# PDB_Schematic_v1_0.net
KiCad netlist of a schematic drawn in Altium Designer
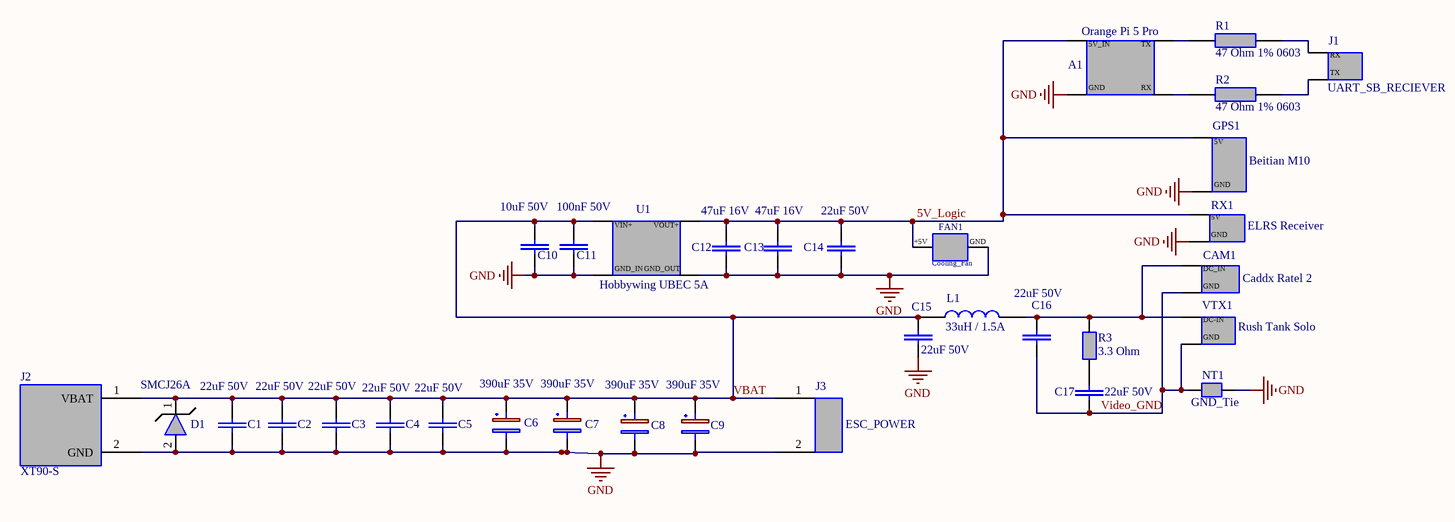
[diagram p0: PDB_Schematic_v1.0.SchDoc]

(export (version "E")
  (design (tool "Eeschema 10.0.6"))
  (components
    (comp (ref "A1")
      (value "Orange Pi 5 Pro")
      (footprint "PDB_Footprints_v1.0:FOOTPRINT_ORANGE_PI")
      (libsource (lib "PDB_Components_v1.0") (part "Orange Pi 5 Pro"))
    )
    (comp (ref "C1")
      (value "22uF 50V")
      (footprint "PDB_Footprints_v1.0:1210")
      (libsource (lib "PDB_Components_v1.0") (part "Cap_MLCC"))
    )
    (comp (ref "C2")
      (value "22uF 50V")
      (footprint "PDB_Footprints_v1.0:1210")
      (libsource (lib "PDB_Components_v1.0") (part "Cap_MLCC"))
    )
    (comp (ref "C3")
      (value "22uF 50V")
      (footprint "PDB_Footprints_v1.0:1210")
      (libsource (lib "PDB_Components_v1.0") (part "Cap_MLCC"))
    )
    (comp (ref "C4")
      (value "22uF 50V")
      (footprint "PDB_Footprints_v1.0:1210")
      (libsource (lib "PDB_Components_v1.0") (part "Cap_Cer_22uF_50V"))
    )
    (comp (ref "C5")
      (value "22uF 50V")
      (footprint "PDB_Footprints_v1.0:1210")
      (libsource (lib "PDB_Components_v1.0") (part "Cap_MLCC"))
    )
    (comp (ref "C6")
      (value "390uF 35V")
      (footprint "PDB_Footprints_v1.0:CAP_ELEC_D10.0_P5.0")
      (description "Low ESR Aluminum Electrolytic Capacitor, Panasonic FR Series, 390uF 35V, Radial, 5mm Lead Pitc")
      (fields (field (name "VOLTAGE") "35V") (field (name "MANUFACTURER") "Panasonic"))
      (libsource (lib "PDB_Components_v1.0") (part "Cap_Low_ESR"))
    )
    (comp (ref "C7")
      (value "390uF 35V")
      (footprint "PDB_Footprints_v1.0:CAP_ELEC_D10.0_P5.0")
      (description "Low ESR Aluminum Electrolytic Capacitor, Panasonic FR Series, 390uF 35V, Radial, 5mm Lead Pitc")
      (fields (field (name "VOLTAGE") "35V") (field (name "MANUFACTURER") "Panasonic"))
      (libsource (lib "PDB_Components_v1.0") (part "Cap_Low_ESR"))
    )
    (comp (ref "C8")
      (value "390uF 35V")
      (footprint "PDB_Footprints_v1.0:CAP_ELEC_D10.0_P5.0")
      (description "Low ESR Aluminum Electrolytic Capacitor, Panasonic FR Series, 390uF 35V, Radial, 5mm Lead Pitc")
      (fields (field (name "VOLTAGE") "35V") (field (name "MANUFACTURER") "Panasonic"))
      (libsource (lib "PDB_Components_v1.0") (part "Cap_Low_ESR"))
    )
    (comp (ref "C9")
      (value "390uF 35V")
      (footprint "PDB_Footprints_v1.0:CAP_ELEC_D10.0_P5.0")
      (description "Low ESR Aluminum Electrolytic Capacitor, Panasonic FR Series, 390uF 35V, Radial, 5mm Lead Pitc")
      (fields (field (name "VOLTAGE") "35V") (field (name "MANUFACTURER") "Panasonic"))
      (libsource (lib "PDB_Components_v1.0") (part "Cap_Low_ESR"))
    )
    (comp (ref "C10")
      (value "10uF 50V")
      (footprint "PDB_Footprints_v1.0:1206")
      (description "Ceramic Capacitor, 10 uF, 50 V, X7R Dielectric, 1206 SMD, UBEC VIN Buffer")
      (libsource (lib "PDB_Components_v1.0") (part "Cap_Cer_10uF_50V_1206"))
    )
    (comp (ref "C11")
      (value "100nF 50V")
      (footprint "PDB_Footprints_v1.0:0603")
      (description "High-Frequency Ceramic Capacitor, 100 nF, 50 V, X7R Dielectric, 0603 SMD, UBEC VIN Decoupling")
      (libsource (lib "PDB_Components_v1.0") (part "Cap_Cer_100nF_50V_0603"))
    )
    (comp (ref "C12")
      (value "47uF 16V")
      (footprint "PDB_Footprints_v1.0:1210")
      (description "Capacitor MLCC 47uF 16V X7R 1210\r\nGRM32ER71C476KE15L")
      (libsource (lib "PDB_Components_v1.0") (part "Cap_Cer_47uF_16V"))
    )
    (comp (ref "C13")
      (value "47uF 16V")
      (footprint "PDB_Footprints_v1.0:1210")
      (description "Capacitor MLCC 47uF 16V X7R 1210\r\nGRM32ER71C476KE15L")
      (libsource (lib "PDB_Components_v1.0") (part "Cap_Cer_47uF_16V"))
    )
    (comp (ref "C14")
      (value "22uF 50V")
      (footprint "PDB_Footprints_v1.0:1210")
      (description "Multilayer Ceramic Capacitor (MLCC), 22uF 50V, X7R, 1210 (3225 Metric), High-Frequency ESC Filter")
      (libsource (lib "PDB_Components_v1.0") (part "Cap_MLCC"))
    )
    (comp (ref "C15")
      (value "22uF 50V")
      (footprint "PDB_Footprints_v1.0:1210")
      (libsource (lib "PDB_Components_v1.0") (part "Cap_Cer_22uF_50V"))
    )
    (comp (ref "C16")
      (value "22uF 50V")
      (footprint "PDB_Footprints_v1.0:1210")
      (libsource (lib "PDB_Components_v1.0") (part "Cap_Cer_22uF_50V"))
    )
    (comp (ref "C17")
      (value "22uF 50V")
      (footprint "PDB_Footprints_v1.0:1206")
      (description "Capacitor MLCC 22uF 50V ±20% X7R 1206 (3216 Metric)")
      (libsource (lib "PDB_Components_v1.0") (part "Cap_Cer_22uF_50V_1206"))
    )
    (comp (ref "CAM1")
      (value "Caddx Ratel 2")
      (footprint "PDB_Footprints_v1.0:FOOTPRINT_Caddx_Ratel_2")
      (description "Analog FPV Micro Camera, 1200TVL, Ultra Low Light Starlight")
      (libsource (lib "PDB_Components_v1.0") (part "Caddx Ratel 2"))
    )
    (comp (ref "D1")
      (value "SMCJ26A")
      (footprint "PDB_Footprints_v1.0:DIODE_SMC")
      (description "Transient Voltage Suppressor (TVS) Diode, Unidirectional, 26V Vrwm, 1500W Peak, DO-214AB (SMC)")
      (libsource (lib "PDB_Components_v1.0") (part "SMCJ26A"))
    )
    (comp (ref "FAN1")
      (value "Cooling_Fan")
      (footprint "PDB_Footprints_v1.0:FOOTPRINT_FAN_5V")
      (description "V DC Micro Cooling Fan, 25x25x10mm Active Cooling")
      (libsource (lib "PDB_Components_v1.0") (part "Cooling Fan 5V"))
    )
    (comp (ref "GPS1")
      (value "Beitian M10")
      (footprint "PDB_Footprints_v1.0:FOOTPRINT_BEITIAN_M10")
      (description "GNSS GPS + Compass Module, M10 Platform, UART & I2C Interface")
      (libsource (lib "PDB_Components_v1.0") (part "Beitian M10"))
    )
    (comp (ref "J1")
      (value "UART_SB_RECIEVER")
      (footprint "PDB_Footprints_v1.0:UART_SPEEDYBEE_RECIEVER")
      (libsource (lib "PDB_Components_v1.0") (part "UART_SPEEDYBEE_RECIEVER"))
    )
    (comp (ref "J2")
      (value "XT90-S")
      (footprint "PDB_Footprints_v1.0:XT90-S_PWR")
      (description "High-Current DC Power Connector with Integrated Anti-Spark Resistance, Amass XT90-S, 90A Peak")
      (libsource (lib "PDB_Components_v1.0") (part "XT90-S"))
    )
    (comp (ref "J3")
      (value "ESC_POWER")
      (footprint "PDB_Footprints_v1.0:PADS_ESC_PWR")
      (description "Wire-to-Board Solder Pads Array, 1x2, 2.54mm Pitch")
      (libsource (lib "PDB_Components_v1.0") (part "PADS_WIRE_1X2"))
    )
    (comp (ref "L1")
      (value "33uH / 1.5A")
      (footprint "PDB_Footprints_v1.0:FOOTPRINT_INDUCTOR_SRN6045")
      (description "Semi-Shielded Power Inductor, Bourns SRN6045 Series, 33uH 2.5A, 0.15 Ohm DCR, LC Video Filter")
      (fields (field (name "MANUFACTURER") "Bourns") (field (name "MANUFACTURER PART NUMBER") "SRN6045-330M"))
      (libsource (lib "PDB_Components_v1.0") (part "Inductor_SMD"))
    )
    (comp (ref "NT1")
      (value "GND_Tie")
      (footprint "PDB_Footprints_v1.0:NET_TIE_0.2MM")
      (description "Net-Tie zero-ohm bridge for ground separation")
      (libsource (lib "PDB_Components_v1.0") (part "NET_TIE"))
    )
    (comp (ref "R1")
      (value "47 Ohm 1% 0603")
      (footprint "PDB_Footprints_v1.0:0603")
      (fields (field (name "PART NUMBER") "RC0603FR-0747RL") (field (name "MANUFACTURER") "Yageo"))
      (libsource (lib "PDB_Components_v1.0") (part "Res_SMD"))
    )
    (comp (ref "R2")
      (value "47 Ohm 1% 0603")
      (footprint "PDB_Footprints_v1.0:0603")
      (fields (field (name "PART NUMBER") "RC0603FR-0747RL") (field (name "MANUFACTURER") "Yageo"))
      (libsource (lib "PDB_Components_v1.0") (part "Res_SMD"))
    )
    (comp (ref "R3")
      (value "3.3 Ohm")
      (footprint "PDB_Footprints_v1.0:0603")
      (description "Resistor SMD 3.3 Ohm 1% 1/10W (0.1W) 0603 Thick Film")
      (libsource (lib "PDB_Components_v1.0") (part "Res_3.3Ohm_0603"))
    )
    (comp (ref "RX1")
      (value "ELRS Receiver")
      (footprint "PDB_Footprints_v1.0:FOOTPRINT_ELRS_RX")
      (description "ExpressLRS 2.4GHz True Diversity Radio Receiver Module")
      (libsource (lib "PDB_Components_v1.0") (part "ExpressLRS RX"))
    )
    (comp (ref "U1")
      (value "Hobbywing UBEC 5A")
      (footprint "PDB_Footprints_v1.0:UBEC_Hobbywing_5A")
      (fields (field (name "MANUFACTURER") "Hobbywing") (field (name "PART NUMBER") "HW30607000"))
      (libsource (lib "PDB_Components_v1.0") (part "UBEC_Hobbywing_5A"))
    )
    (comp (ref "VTX1")
      (value "Rush Tank Solo")
      (footprint "PDB_Footprints_v1.0:FOOTPRINT_VTX_RUSH_SOLO")
      (description "5.8GHz VTX 1.6W Video Transmitter Module")
      (libsource (lib "PDB_Components_v1.0") (part "Rush Tank Solo 1.6W"))
    )
  )
  (nets
    (net (code "1") (name "/5V_Logic") (class "Default")
      (node (ref "A1") (pin "1") (pinfunction "5V_IN_1") (pintype "power_in"))
      (node (ref "C12") (pin "2") (pinfunction "-_2") (pintype "passive"))
      (node (ref "C13") (pin "2") (pinfunction "-_2") (pintype "passive"))
      (node (ref "C14") (pin "2") (pinfunction "-_2") (pintype "passive"))
      (node (ref "FAN1") (pin "1") (pinfunction "+5V_1") (pintype "power_in"))
      (node (ref "GPS1") (pin "1") (pinfunction "5V_1") (pintype "power_in"))
      (node (ref "RX1") (pin "1") (pinfunction "5V_1") (pintype "power_in"))
      (node (ref "U1") (pin "2") (pinfunction "+5.1V_2") (pintype "power_in"))
    )
    (net (code "3") (name "/VBAT") (class "Default")
      (node (ref "C1") (pin "2") (pinfunction "-_2") (pintype "passive"))
      (node (ref "C10") (pin "2") (pinfunction "-_2") (pintype "passive"))
      (node (ref "C11") (pin "2") (pinfunction "-_2") (pintype "passive"))
      (node (ref "C15") (pin "2") (pinfunction "-_2") (pintype "passive"))
      (node (ref "C2") (pin "2") (pinfunction "-_2") (pintype "passive"))
      (node (ref "C3") (pin "2") (pinfunction "-_2") (pintype "passive"))
      (node (ref "C4") (pin "2") (pinfunction "-_2") (pintype "passive"))
      (node (ref "C5") (pin "2") (pinfunction "-_2") (pintype "passive"))
      (node (ref "C6") (pin "1") (pinfunction "+_1") (pintype "passive"))
      (node (ref "C7") (pin "1") (pinfunction "+_1") (pintype "passive"))
      (node (ref "C8") (pin "1") (pinfunction "+_1") (pintype "passive"))
      (node (ref "C9") (pin "1") (pinfunction "+_1") (pintype "passive"))
      (node (ref "D1") (pin "1") (pinfunction "k_1") (pintype "power_in"))
      (node (ref "J2") (pin "1") (pinfunction "VBAT_1") (pintype "power_in"))
      (node (ref "J3") (pin "1") (pintype "passive"))
      (node (ref "L1") (pin "1") (pinfunction "1_1") (pintype "passive"))
      (node (ref "U1") (pin "1") (pinfunction "VIN+_1") (pintype "power_in"))
    )
    (net (code "4") (name "/Video_GND") (class "Default")
      (node (ref "C16") (pin "1") (pinfunction "+_1") (pintype "passive"))
      (node (ref "C17") (pin "1") (pinfunction "+_1") (pintype "passive"))
      (node (ref "CAM1") (pin "2") (pinfunction "GND_2") (pintype "power_in"))
      (node (ref "NT1") (pin "2") (pinfunction "Video_GND_2") (pintype "power_in"))
      (node (ref "VTX1") (pin "2") (pinfunction "GND_2") (pintype "power_in"))
    )
    (net (code "5") (name "GND") (class "Default")
      (node (ref "A1") (pin "2") (pinfunction "GND_2") (pintype "power_in"))
      (node (ref "C1") (pin "1") (pinfunction "+_1") (pintype "passive"))
      (node (ref "C10") (pin "1") (pinfunction "+_1") (pintype "passive"))
      (node (ref "C11") (pin "1") (pinfunction "+_1") (pintype "passive"))
      (node (ref "C12") (pin "1") (pinfunction "+_1") (pintype "passive"))
      (node (ref "C13") (pin "1") (pinfunction "+_1") (pintype "passive"))
      (node (ref "C14") (pin "1") (pinfunction "+_1") (pintype "passive"))
      (node (ref "C15") (pin "1") (pinfunction "+_1") (pintype "passive"))
      (node (ref "C2") (pin "1") (pinfunction "+_1") (pintype "passive"))
      (node (ref "C3") (pin "1") (pinfunction "+_1") (pintype "passive"))
      (node (ref "C4") (pin "1") (pinfunction "+_1") (pintype "passive"))
      (node (ref "C5") (pin "1") (pinfunction "+_1") (pintype "passive"))
      (node (ref "C6") (pin "2") (pinfunction "-_2") (pintype "passive"))
      (node (ref "C7") (pin "2") (pinfunction "-_2") (pintype "passive"))
      (node (ref "C8") (pin "2") (pinfunction "-_2") (pintype "passive"))
      (node (ref "C9") (pin "2") (pinfunction "-_2") (pintype "passive"))
      (node (ref "D1") (pin "2") (pinfunction "A_2") (pintype "power_in"))
      (node (ref "FAN1") (pin "2") (pinfunction "GND_2") (pintype "passive"))
      (node (ref "GPS1") (pin "2") (pinfunction "GND_2") (pintype "power_in"))
      (node (ref "J2") (pin "2") (pinfunction "GND_2") (pintype "power_in"))
      (node (ref "J3") (pin "2") (pintype "passive"))
      (node (ref "NT1") (pin "1") (pinfunction "GND_1") (pintype "power_in"))
      (node (ref "RX1") (pin "2") (pinfunction "GND_2") (pintype "power_in"))
      (node (ref "U1") (pin "3") (pinfunction "GND_IN_3") (pintype "power_in"))
      (node (ref "U1") (pin "4") (pinfunction "GND_OUT_4") (pintype "power_in"))
    )
    (net (code "6") (name "Net-(A1-+5.1V)") (class "Default")
      (node (ref "A1") (pin "3") (pinfunction "+5.1V_3") (pintype "passive"))
      (node (ref "R1") (pin "1") (pinfunction "1_1") (pintype "passive"))
    )
    (net (code "7") (name "Net-(A1-RX)") (class "Default")
      (node (ref "A1") (pin "4") (pinfunction "RX_4") (pintype "passive"))
      (node (ref "R2") (pin "1") (pinfunction "1_1") (pintype "passive"))
    )
    (net (code "8") (name "Net-(C16--)") (class "Default")
      (node (ref "C16") (pin "2") (pinfunction "-_2") (pintype "passive"))
      (node (ref "CAM1") (pin "1") (pinfunction "DC_IN_1") (pintype "power_in"))
      (node (ref "L1") (pin "2") (pinfunction "2_2") (pintype "passive"))
      (node (ref "R3") (pin "2") (pinfunction "2_2") (pintype "passive"))
      (node (ref "VTX1") (pin "1") (pinfunction "(7-36V)_1") (pintype "power_in"))
    )
    (net (code "9") (name "Net-(C17--)") (class "Default")
      (node (ref "C17") (pin "2") (pinfunction "-_2") (pintype "passive"))
      (node (ref "R3") (pin "1") (pinfunction "1_1") (pintype "passive"))
    )
    (net (code "10") (name "Net-(J1-RX)") (class "Default")
      (node (ref "J1") (pin "1") (pinfunction "RX_1") (pintype "power_in"))
      (node (ref "R1") (pin "2") (pinfunction "2_2") (pintype "passive"))
    )
    (net (code "11") (name "Net-(J1-TX)") (class "Default")
      (node (ref "J1") (pin "2") (pinfunction "TX_2") (pintype "power_in"))
      (node (ref "R2") (pin "2") (pinfunction "2_2") (pintype "passive"))
    )
  )
)
